# wt11_uart_breakout_board_v10.net
KiCad netlist of a schematic drawn in EAGLE
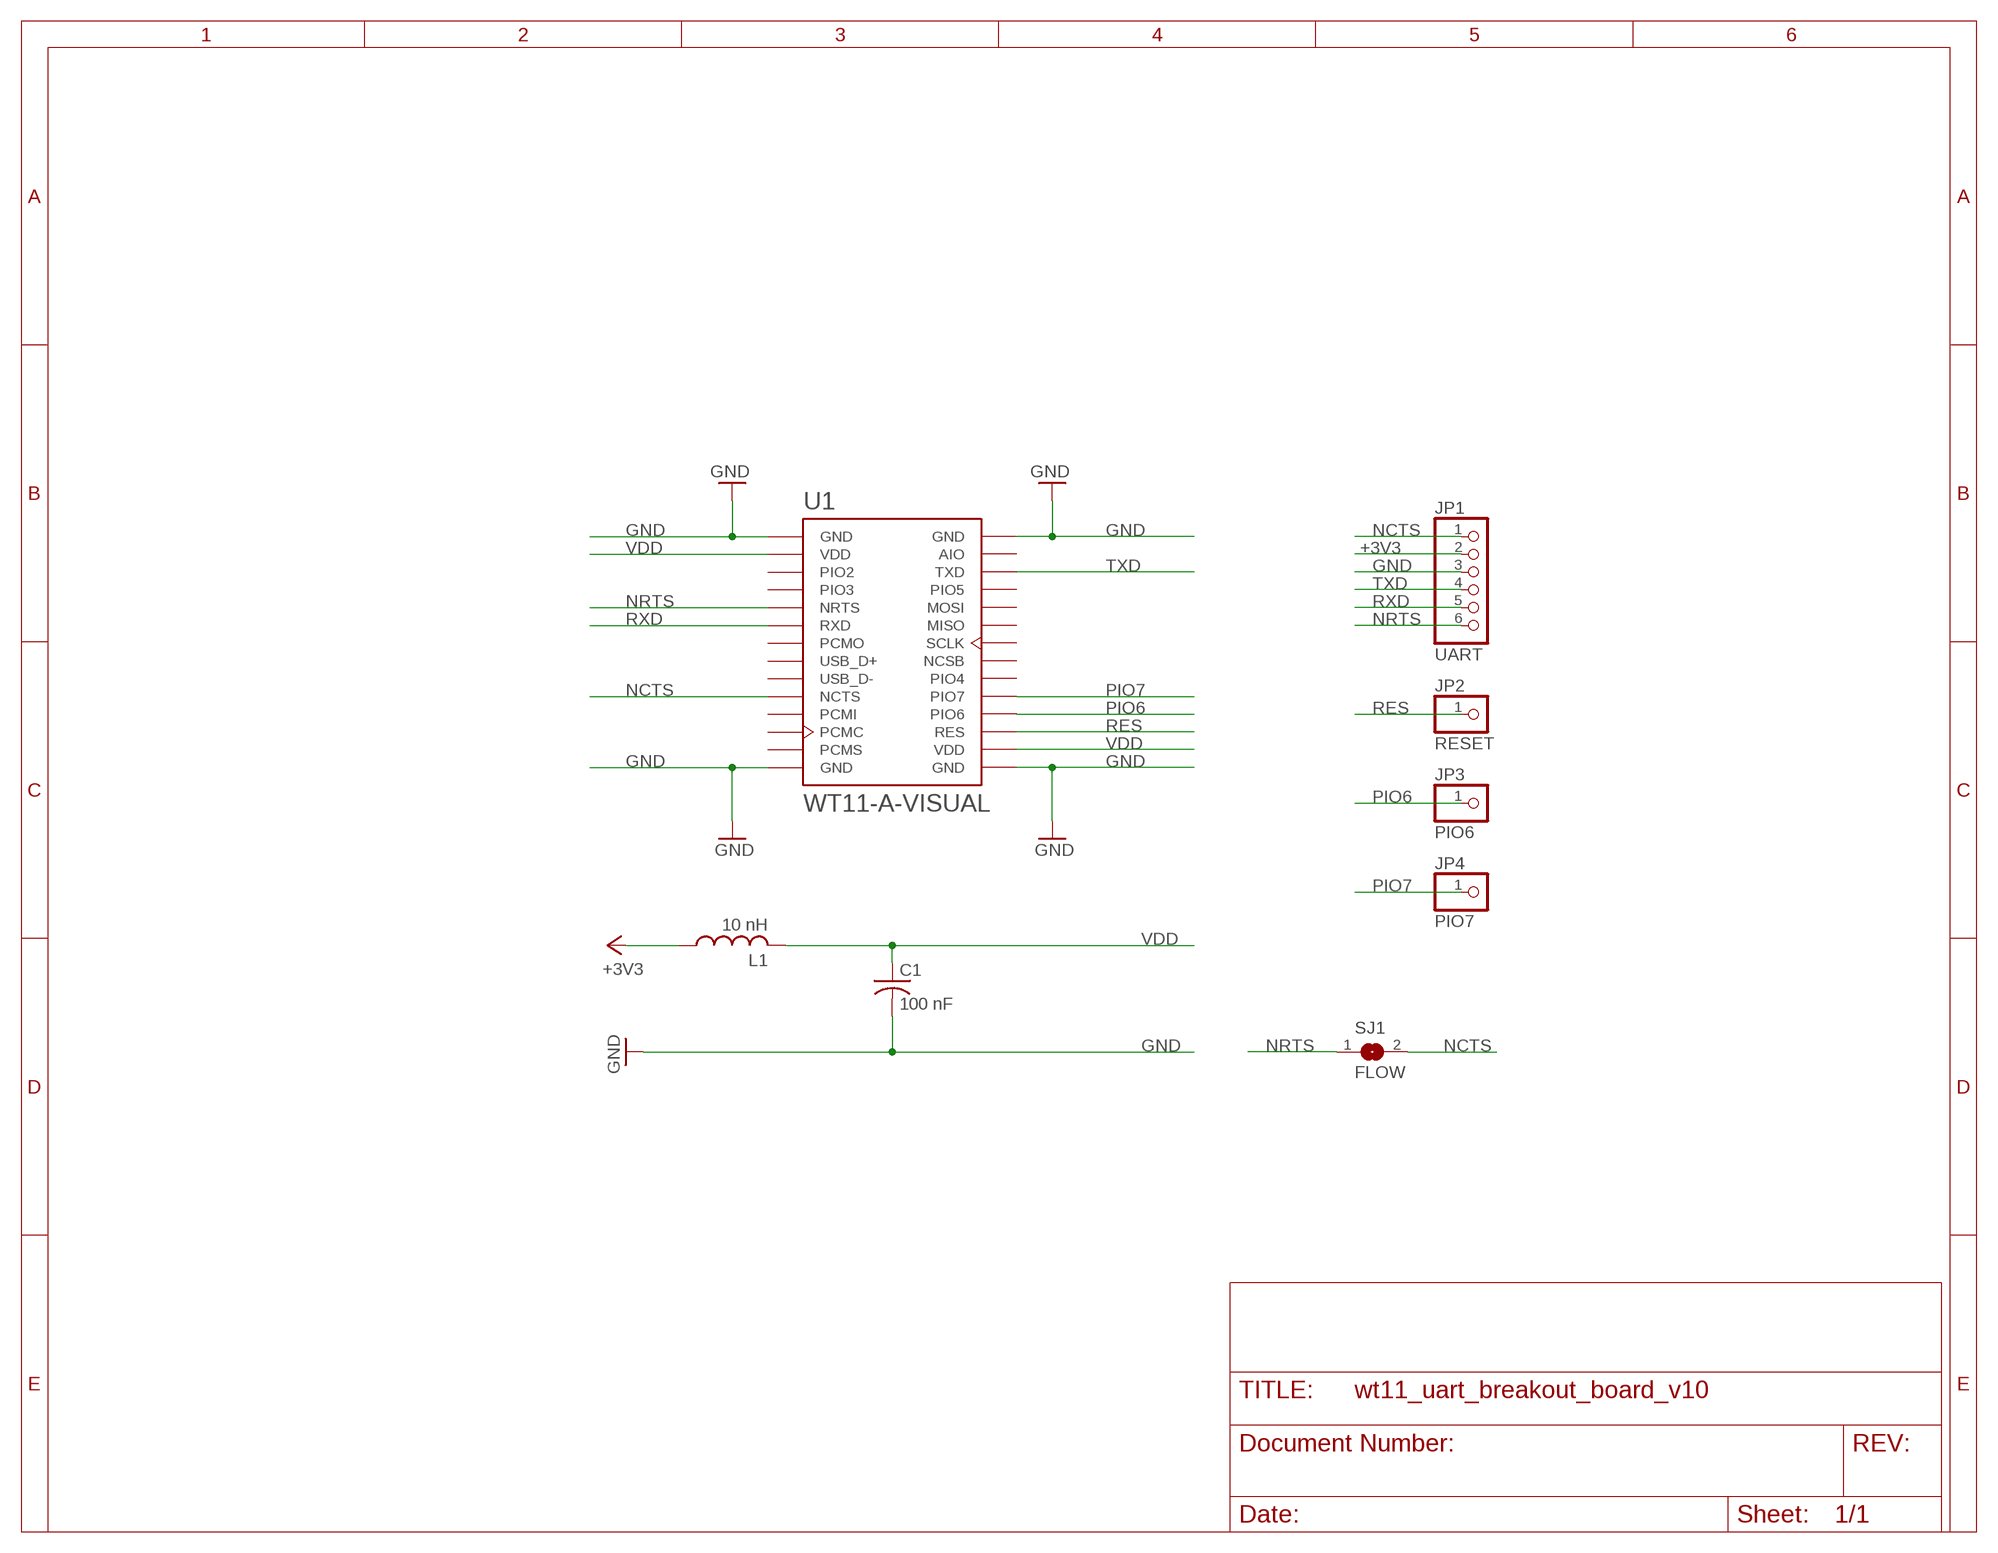
[diagram p0: schematic, sheet 1]

(export (version "E")
  (design (tool "Eeschema 10.0.6"))
  (components
    (comp (ref "C1")
      (value "100 nF")
      (footprint "eagle-import:C0603K")
      (libsource (lib "eagle-import") (part "C-USC0603K"))
    )
    (comp (ref "JP1")
      (value "UART")
      (footprint "eagle-import:1X06")
      (libsource (lib "eagle-import") (part "PINHD-1X6"))
    )
    (comp (ref "JP2")
      (value "RESET")
      (footprint "eagle-import:1X01")
      (libsource (lib "eagle-import") (part "PINHD-1X1"))
    )
    (comp (ref "JP3")
      (value "PIO6")
      (footprint "eagle-import:1X01")
      (libsource (lib "eagle-import") (part "PINHD-1X1"))
    )
    (comp (ref "JP4")
      (value "PIO7")
      (footprint "eagle-import:1X01")
      (libsource (lib "eagle-import") (part "PINHD-1X1"))
    )
    (comp (ref "L1")
      (value "10 nH")
      (footprint "eagle-import:L2012C")
      (libsource (lib "eagle-import") (part "L-USL2012C"))
    )
    (comp (ref "SJ1")
      (value "FLOW")
      (footprint "eagle-import:SJ")
      (libsource (lib "eagle-import") (part "SJ"))
    )
    (comp (ref "U1")
      (value "WT11-A-VISUAL")
      (footprint "eagle-import:WT11-A")
      (libsource (lib "eagle-import") (part "WT11-A-VISUAL"))
    )
  )
  (nets
    (net (code "1") (name "+3V3") (class "Default")
      (node (ref "JP1") (pin "2") (pinfunction "2_2") (pintype "passive"))
      (node (ref "L1") (pin "1") (pinfunction "1_1") (pintype "passive"))
    )
    (net (code "2") (name "/NCTS") (class "Default")
      (node (ref "JP1") (pin "1") (pinfunction "1_1") (pintype "passive"))
      (node (ref "SJ1") (pin "2") (pinfunction "2_2") (pintype "passive"))
      (node (ref "U1") (pin "NCTS") (pinfunction "NCTS_NCTS") (pintype "input"))
    )
    (net (code "3") (name "/NRTS") (class "Default")
      (node (ref "JP1") (pin "6") (pinfunction "6_6") (pintype "passive"))
      (node (ref "SJ1") (pin "1") (pinfunction "1_1") (pintype "passive"))
      (node (ref "U1") (pin "NRTS") (pinfunction "NRTS_NRTS") (pintype "output"))
    )
    (net (code "4") (name "/PIO6") (class "Default")
      (node (ref "JP3") (pin "1") (pinfunction "1_1") (pintype "passive"))
      (node (ref "U1") (pin "PIO6") (pinfunction "PIO6_PIO6") (pintype "bidirectional"))
    )
    (net (code "5") (name "/PIO7") (class "Default")
      (node (ref "JP4") (pin "1") (pinfunction "1_1") (pintype "passive"))
      (node (ref "U1") (pin "PIO7") (pinfunction "PIO7_PIO7") (pintype "bidirectional"))
    )
    (net (code "6") (name "/RES") (class "Default")
      (node (ref "JP2") (pin "1") (pinfunction "1_1") (pintype "passive"))
      (node (ref "U1") (pin "RES") (pinfunction "RES_RES") (pintype "input"))
    )
    (net (code "7") (name "/RXD") (class "Default")
      (node (ref "JP1") (pin "5") (pinfunction "5_5") (pintype "passive"))
      (node (ref "U1") (pin "RXD") (pinfunction "RXD_RXD") (pintype "input"))
    )
    (net (code "8") (name "/TXD") (class "Default")
      (node (ref "JP1") (pin "4") (pinfunction "4_4") (pintype "passive"))
      (node (ref "U1") (pin "TXD") (pinfunction "TXD_TXD") (pintype "output"))
    )
    (net (code "9") (name "/VDD") (class "Default")
      (node (ref "C1") (pin "1") (pinfunction "1_1") (pintype "passive"))
      (node (ref "L1") (pin "2") (pinfunction "2_2") (pintype "passive"))
      (node (ref "U1") (pin "VDD1") (pinfunction "VDD_VDD1") (pintype "power_in"))
      (node (ref "U1") (pin "VDD2") (pinfunction "VDD_VDD2") (pintype "power_in"))
    )
    (net (code "10") (name "GND") (class "Default")
      (node (ref "C1") (pin "2") (pinfunction "2_2") (pintype "passive"))
      (node (ref "JP1") (pin "3") (pinfunction "3_3") (pintype "passive"))
      (node (ref "U1") (pin "GND1") (pinfunction "GND_GND1") (pintype "power_in"))
      (node (ref "U1") (pin "GND2") (pinfunction "GND_GND2") (pintype "power_in"))
      (node (ref "U1") (pin "GND3") (pinfunction "GND_GND3") (pintype "power_in"))
      (node (ref "U1") (pin "GND4") (pinfunction "GND_GND4") (pintype "power_in"))
    )
    (net (code "11") (name "unconnected-(U1-PadAIO)") (class "Default")
      (node (ref "U1") (pin "AIO") (pinfunction "AIO_AIO") (pintype "bidirectional"))
    )
    (net (code "12") (name "unconnected-(U1-PadMISO)") (class "Default")
      (node (ref "U1") (pin "MISO") (pinfunction "MISO_MISO") (pintype "output"))
    )
    (net (code "13") (name "unconnected-(U1-PadMOSI)") (class "Default")
      (node (ref "U1") (pin "MOSI") (pinfunction "MOSI_MOSI") (pintype "input"))
    )
    (net (code "14") (name "unconnected-(U1-PadNCSB)") (class "Default")
      (node (ref "U1") (pin "NCSB") (pinfunction "NCSB_NCSB") (pintype "input"))
    )
    (net (code "15") (name "unconnected-(U1-PadPCMC)") (class "Default")
      (node (ref "U1") (pin "PCMC") (pinfunction "PCMC_PCMC") (pintype "bidirectional"))
    )
    (net (code "16") (name "unconnected-(U1-PadPCMI)") (class "Default")
      (node (ref "U1") (pin "PCMI") (pinfunction "PCMI_PCMI") (pintype "input"))
    )
    (net (code "17") (name "unconnected-(U1-PadPCMO)") (class "Default")
      (node (ref "U1") (pin "PCMO") (pinfunction "PCMO_PCMO") (pintype "output"))
    )
    (net (code "18") (name "unconnected-(U1-PadPCMS)") (class "Default")
      (node (ref "U1") (pin "PCMS") (pinfunction "PCMS_PCMS") (pintype "bidirectional"))
    )
    (net (code "19") (name "unconnected-(U1-PadPIO2)") (class "Default")
      (node (ref "U1") (pin "PIO2") (pinfunction "PIO2_PIO2") (pintype "bidirectional"))
    )
    (net (code "20") (name "unconnected-(U1-PadPIO3)") (class "Default")
      (node (ref "U1") (pin "PIO3") (pinfunction "PIO3_PIO3") (pintype "bidirectional"))
    )
    (net (code "21") (name "unconnected-(U1-PadPIO4)") (class "Default")
      (node (ref "U1") (pin "PIO4") (pinfunction "PIO4_PIO4") (pintype "bidirectional"))
    )
    (net (code "22") (name "unconnected-(U1-PadPIO5)") (class "Default")
      (node (ref "U1") (pin "PIO5") (pinfunction "PIO5_PIO5") (pintype "bidirectional"))
    )
    (net (code "23") (name "unconnected-(U1-PadSCLK)") (class "Default")
      (node (ref "U1") (pin "SCLK") (pinfunction "SCLK_SCLK") (pintype "input"))
    )
    (net (code "24") (name "unconnected-(U1-PadUSB_D+)") (class "Default")
      (node (ref "U1") (pin "USB_D+") (pinfunction "USB_D+_USB_D+") (pintype "bidirectional"))
    )
    (net (code "25") (name "unconnected-(U1-PadUSB_D-)") (class "Default")
      (node (ref "U1") (pin "USB_D-") (pinfunction "USB_D-_USB_D-") (pintype "bidirectional"))
    )
  )
)
